# test_brd_gnd.net
KiCad netlist of a schematic drawn in EAGLE
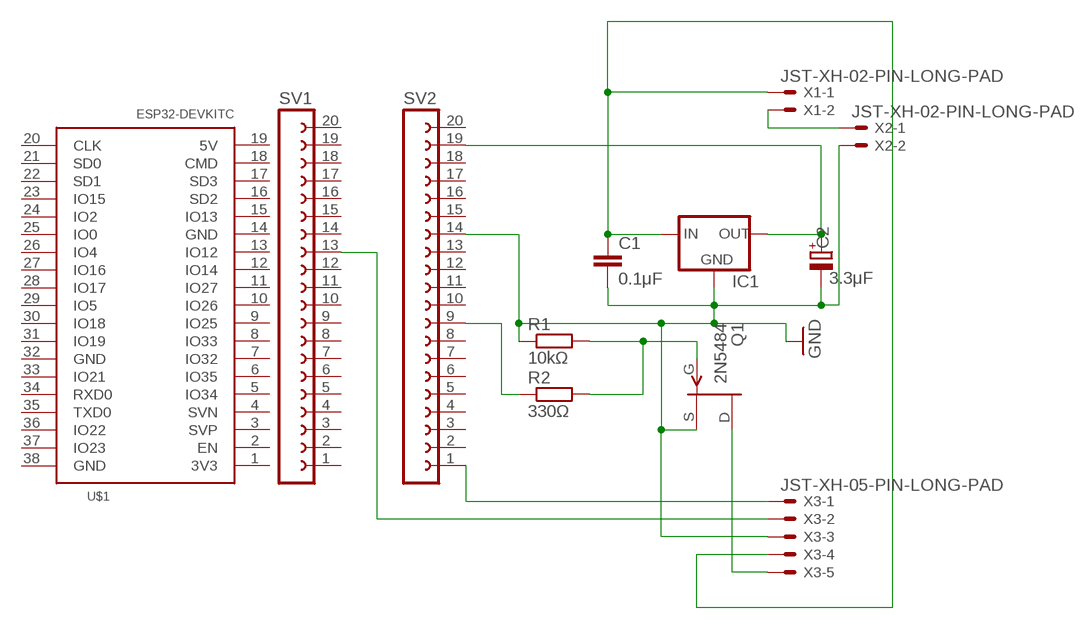
[diagram p0: schematic, sheet 1]

(export (version "E")
  (design (tool "Eeschema 10.0.6"))
  (components
    (comp (ref "C1")
      (value "0.1μF")
      (footprint "eagle-import:C025-040X050")
      (libsource (lib "eagle-import") (part "C-EU025-040X050"))
    )
    (comp (ref "C2")
      (value "3.3μF")
      (footprint "eagle-import:E2,5-5")
      (libsource (lib "eagle-import") (part "CPOL-EUE2.5-5"))
    )
    (comp (ref "IC1")
      (value "78XXS")
      (footprint "eagle-import:78XXS")
      (libsource (lib "eagle-import") (part "78XXS"))
    )
    (comp (ref "Q1")
      (value "2N5484")
      (footprint "eagle-import:TO92-")
      (libsource (lib "eagle-import") (part "?5482N4"))
    )
    (comp (ref "R1")
      (value "10kΩ")
      (footprint "eagle-import:0207_10")
      (libsource (lib "eagle-import") (part "R-EU_0207/10"))
    )
    (comp (ref "R2")
      (value "330Ω")
      (footprint "eagle-import:0207_10")
      (libsource (lib "eagle-import") (part "R-EU_0207/10"))
    )
    (comp (ref "SV1")
      (value "FE20-1")
      (footprint "eagle-import:FE20")
      (libsource (lib "eagle-import") (part "FE20-1"))
    )
    (comp (ref "SV2")
      (value "FE20-1")
      (footprint "eagle-import:FE20")
      (libsource (lib "eagle-import") (part "FE20-1"))
    )
    (comp (ref "U$1")
      (value "ESP32DEVKITC")
      (footprint "eagle-import:ESP32-DEVKITC")
      (libsource (lib "eagle-import") (part "ESP32DEVKITC"))
    )
    (comp (ref "X1")
      (value "JST-XH-02-PIN-LONG-PAD")
      (footprint "eagle-import:JST-XH-02-PACKAGE-LONG-PAD")
      (libsource (lib "eagle-import") (part "JST-XH-02-PIN-LONG-PAD"))
    )
    (comp (ref "X2")
      (value "JST-XH-02-PIN-LONG-PAD")
      (footprint "eagle-import:JST-XH-02-PACKAGE-LONG-PAD")
      (libsource (lib "eagle-import") (part "JST-XH-02-PIN-LONG-PAD"))
    )
    (comp (ref "X3")
      (value "JST-XH-05-PIN-LONG-PAD")
      (footprint "eagle-import:JST-XH-05-PACKAGE-LONG-PAD")
      (libsource (lib "eagle-import") (part "JST-XH-05-PIN-LONG-PAD"))
    )
  )
  (nets
    (net (code "1") (name "GND") (class "Default")
      (node (ref "C1") (pin "2") (pinfunction "2_2") (pintype "passive"))
      (node (ref "C2") (pin "-") (pinfunction "-_-") (pintype "passive"))
      (node (ref "IC1") (pin "GND") (pinfunction "GND_GND") (pintype "input"))
      (node (ref "Q1") (pin "2") (pinfunction "S_2") (pintype "passive"))
      (node (ref "R1") (pin "1") (pinfunction "1_1") (pintype "passive"))
      (node (ref "SV2") (pin "14") (pinfunction "14_14") (pintype "passive"))
      (node (ref "X2") (pin "2") (pinfunction "S_2") (pintype "passive"))
      (node (ref "X3") (pin "3") (pinfunction "S_3") (pintype "passive"))
    )
    (net (code "2") (name "Net-(C2-Pad+)") (class "Default")
      (node (ref "C2") (pin "+") (pinfunction "+_+") (pintype "passive"))
      (node (ref "IC1") (pin "OUT") (pinfunction "OUT_OUT") (pintype "passive"))
      (node (ref "SV2") (pin "19") (pinfunction "19_19") (pintype "passive"))
    )
    (net (code "3") (name "Net-(Q1-D)") (class "Default")
      (node (ref "Q1") (pin "3") (pinfunction "D_3") (pintype "passive"))
      (node (ref "X3") (pin "5") (pinfunction "S_5") (pintype "passive"))
    )
    (net (code "4") (name "Net-(Q1-G)") (class "Default")
      (node (ref "Q1") (pin "1") (pinfunction "G_1") (pintype "passive"))
      (node (ref "R1") (pin "2") (pinfunction "2_2") (pintype "passive"))
      (node (ref "R2") (pin "2") (pinfunction "2_2") (pintype "passive"))
    )
    (net (code "5") (name "Net-(R2-Pad1)") (class "Default")
      (node (ref "R2") (pin "1") (pinfunction "1_1") (pintype "passive"))
      (node (ref "SV2") (pin "9") (pinfunction "9_9") (pintype "passive"))
    )
    (net (code "6") (name "Net-(X1A-S)") (class "Default")
      (node (ref "C1") (pin "1") (pinfunction "1_1") (pintype "passive"))
      (node (ref "IC1") (pin "IN") (pinfunction "IN_IN") (pintype "input"))
      (node (ref "X1") (pin "1") (pinfunction "S_1") (pintype "passive"))
      (node (ref "X3") (pin "4") (pinfunction "S_4") (pintype "passive"))
    )
    (net (code "7") (name "Net-(X1B-S)") (class "Default")
      (node (ref "X1") (pin "2") (pinfunction "S_2") (pintype "passive"))
      (node (ref "X2") (pin "1") (pinfunction "S_1") (pintype "passive"))
    )
    (net (code "8") (name "Net-(X3A-S)") (class "Default")
      (node (ref "SV2") (pin "1") (pinfunction "1_1") (pintype "passive"))
      (node (ref "X3") (pin "1") (pinfunction "S_1") (pintype "passive"))
    )
    (net (code "9") (name "Net-(X3B-S)") (class "Default")
      (node (ref "SV1") (pin "13") (pinfunction "13_13") (pintype "passive"))
      (node (ref "X3") (pin "2") (pinfunction "S_2") (pintype "passive"))
    )
    (net (code "10") (name "unconnected-(SV1-Pad1)") (class "Default")
      (node (ref "SV1") (pin "1") (pinfunction "1_1") (pintype "passive"))
    )
    (net (code "11") (name "unconnected-(SV1-Pad2)") (class "Default")
      (node (ref "SV1") (pin "2") (pinfunction "2_2") (pintype "passive"))
    )
    (net (code "12") (name "unconnected-(SV1-Pad3)") (class "Default")
      (node (ref "SV1") (pin "3") (pinfunction "3_3") (pintype "passive"))
    )
    (net (code "13") (name "unconnected-(SV1-Pad4)") (class "Default")
      (node (ref "SV1") (pin "4") (pinfunction "4_4") (pintype "passive"))
    )
    (net (code "14") (name "unconnected-(SV1-Pad5)") (class "Default")
      (node (ref "SV1") (pin "5") (pinfunction "5_5") (pintype "passive"))
    )
    (net (code "15") (name "unconnected-(SV1-Pad6)") (class "Default")
      (node (ref "SV1") (pin "6") (pinfunction "6_6") (pintype "passive"))
    )
    (net (code "16") (name "unconnected-(SV1-Pad7)") (class "Default")
      (node (ref "SV1") (pin "7") (pinfunction "7_7") (pintype "passive"))
    )
    (net (code "17") (name "unconnected-(SV1-Pad8)") (class "Default")
      (node (ref "SV1") (pin "8") (pinfunction "8_8") (pintype "passive"))
    )
    (net (code "18") (name "unconnected-(SV1-Pad9)") (class "Default")
      (node (ref "SV1") (pin "9") (pinfunction "9_9") (pintype "passive"))
    )
    (net (code "19") (name "unconnected-(SV1-Pad10)") (class "Default")
      (node (ref "SV1") (pin "10") (pinfunction "10_10") (pintype "passive"))
    )
    (net (code "20") (name "unconnected-(SV1-Pad11)") (class "Default")
      (node (ref "SV1") (pin "11") (pinfunction "11_11") (pintype "passive"))
    )
    (net (code "21") (name "unconnected-(SV1-Pad12)") (class "Default")
      (node (ref "SV1") (pin "12") (pinfunction "12_12") (pintype "passive"))
    )
    (net (code "22") (name "unconnected-(SV1-Pad14)") (class "Default")
      (node (ref "SV1") (pin "14") (pinfunction "14_14") (pintype "passive"))
    )
    (net (code "23") (name "unconnected-(SV1-Pad15)") (class "Default")
      (node (ref "SV1") (pin "15") (pinfunction "15_15") (pintype "passive"))
    )
    (net (code "24") (name "unconnected-(SV1-Pad16)") (class "Default")
      (node (ref "SV1") (pin "16") (pinfunction "16_16") (pintype "passive"))
    )
    (net (code "25") (name "unconnected-(SV1-Pad17)") (class "Default")
      (node (ref "SV1") (pin "17") (pinfunction "17_17") (pintype "passive"))
    )
    (net (code "26") (name "unconnected-(SV1-Pad18)") (class "Default")
      (node (ref "SV1") (pin "18") (pinfunction "18_18") (pintype "passive"))
    )
    (net (code "27") (name "unconnected-(SV1-Pad19)") (class "Default")
      (node (ref "SV1") (pin "19") (pinfunction "19_19") (pintype "passive"))
    )
    (net (code "28") (name "unconnected-(SV1-Pad20)") (class "Default")
      (node (ref "SV1") (pin "20") (pinfunction "20_20") (pintype "passive"))
    )
    (net (code "29") (name "unconnected-(SV2-Pad2)") (class "Default")
      (node (ref "SV2") (pin "2") (pinfunction "2_2") (pintype "passive"))
    )
    (net (code "30") (name "unconnected-(SV2-Pad3)") (class "Default")
      (node (ref "SV2") (pin "3") (pinfunction "3_3") (pintype "passive"))
    )
    (net (code "31") (name "unconnected-(SV2-Pad4)") (class "Default")
      (node (ref "SV2") (pin "4") (pinfunction "4_4") (pintype "passive"))
    )
    (net (code "32") (name "unconnected-(SV2-Pad5)") (class "Default")
      (node (ref "SV2") (pin "5") (pinfunction "5_5") (pintype "passive"))
    )
    (net (code "33") (name "unconnected-(SV2-Pad6)") (class "Default")
      (node (ref "SV2") (pin "6") (pinfunction "6_6") (pintype "passive"))
    )
    (net (code "34") (name "unconnected-(SV2-Pad7)") (class "Default")
      (node (ref "SV2") (pin "7") (pinfunction "7_7") (pintype "passive"))
    )
    (net (code "35") (name "unconnected-(SV2-Pad8)") (class "Default")
      (node (ref "SV2") (pin "8") (pinfunction "8_8") (pintype "passive"))
    )
    (net (code "36") (name "unconnected-(SV2-Pad10)") (class "Default")
      (node (ref "SV2") (pin "10") (pinfunction "10_10") (pintype "passive"))
    )
    (net (code "37") (name "unconnected-(SV2-Pad11)") (class "Default")
      (node (ref "SV2") (pin "11") (pinfunction "11_11") (pintype "passive"))
    )
    (net (code "38") (name "unconnected-(SV2-Pad12)") (class "Default")
      (node (ref "SV2") (pin "12") (pinfunction "12_12") (pintype "passive"))
    )
    (net (code "39") (name "unconnected-(SV2-Pad13)") (class "Default")
      (node (ref "SV2") (pin "13") (pinfunction "13_13") (pintype "passive"))
    )
    (net (code "40") (name "unconnected-(SV2-Pad15)") (class "Default")
      (node (ref "SV2") (pin "15") (pinfunction "15_15") (pintype "passive"))
    )
    (net (code "41") (name "unconnected-(SV2-Pad16)") (class "Default")
      (node (ref "SV2") (pin "16") (pinfunction "16_16") (pintype "passive"))
    )
    (net (code "42") (name "unconnected-(SV2-Pad17)") (class "Default")
      (node (ref "SV2") (pin "17") (pinfunction "17_17") (pintype "passive"))
    )
    (net (code "43") (name "unconnected-(SV2-Pad18)") (class "Default")
      (node (ref "SV2") (pin "18") (pinfunction "18_18") (pintype "passive"))
    )
    (net (code "44") (name "unconnected-(SV2-Pad20)") (class "Default")
      (node (ref "SV2") (pin "20") (pinfunction "20_20") (pintype "passive"))
    )
    (net (code "45") (name "unconnected-(U$1-3V3-Pad1)") (class "Default")
      (node (ref "U$1") (pin "1") (pinfunction "3V3_1") (pintype "bidirectional"))
    )
    (net (code "46") (name "unconnected-(U$1-5V-Pad19)") (class "Default")
      (node (ref "U$1") (pin "19") (pinfunction "5V_19") (pintype "bidirectional"))
    )
    (net (code "47") (name "unconnected-(U$1-CLK-Pad20)") (class "Default")
      (node (ref "U$1") (pin "20") (pinfunction "CLK_20") (pintype "bidirectional"))
    )
    (net (code "48") (name "unconnected-(U$1-CMD-Pad18)") (class "Default")
      (node (ref "U$1") (pin "18") (pinfunction "CMD_18") (pintype "bidirectional"))
    )
    (net (code "49") (name "unconnected-(U$1-EN-Pad2)") (class "Default")
      (node (ref "U$1") (pin "2") (pinfunction "EN_2") (pintype "bidirectional"))
    )
    (net (code "50") (name "unconnected-(U$1-GND-Pad14)") (class "Default")
      (node (ref "U$1") (pin "14") (pinfunction "GND_14") (pintype "bidirectional"))
    )
    (net (code "51") (name "unconnected-(U$1-GND-Pad32)") (class "Default")
      (node (ref "U$1") (pin "32") (pinfunction "GND_32") (pintype "bidirectional"))
    )
    (net (code "52") (name "unconnected-(U$1-GND-Pad38)") (class "Default")
      (node (ref "U$1") (pin "38") (pinfunction "GND_38") (pintype "bidirectional"))
    )
    (net (code "53") (name "unconnected-(U$1-IO0-Pad25)") (class "Default")
      (node (ref "U$1") (pin "25") (pinfunction "IO0_25") (pintype "bidirectional"))
    )
    (net (code "54") (name "unconnected-(U$1-IO2-Pad24)") (class "Default")
      (node (ref "U$1") (pin "24") (pinfunction "IO2_24") (pintype "bidirectional"))
    )
    (net (code "55") (name "unconnected-(U$1-IO4-Pad26)") (class "Default")
      (node (ref "U$1") (pin "26") (pinfunction "IO4_26") (pintype "bidirectional"))
    )
    (net (code "56") (name "unconnected-(U$1-IO5-Pad29)") (class "Default")
      (node (ref "U$1") (pin "29") (pinfunction "IO5_29") (pintype "bidirectional"))
    )
    (net (code "57") (name "unconnected-(U$1-IO12-Pad13)") (class "Default")
      (node (ref "U$1") (pin "13") (pinfunction "IO12_13") (pintype "bidirectional"))
    )
    (net (code "58") (name "unconnected-(U$1-IO13-Pad15)") (class "Default")
      (node (ref "U$1") (pin "15") (pinfunction "IO13_15") (pintype "bidirectional"))
    )
    (net (code "59") (name "unconnected-(U$1-IO14-Pad12)") (class "Default")
      (node (ref "U$1") (pin "12") (pinfunction "IO14_12") (pintype "bidirectional"))
    )
    (net (code "60") (name "unconnected-(U$1-IO15-Pad23)") (class "Default")
      (node (ref "U$1") (pin "23") (pinfunction "IO15_23") (pintype "bidirectional"))
    )
    (net (code "61") (name "unconnected-(U$1-IO16-Pad27)") (class "Default")
      (node (ref "U$1") (pin "27") (pinfunction "IO16_27") (pintype "bidirectional"))
    )
    (net (code "62") (name "unconnected-(U$1-IO17-Pad28)") (class "Default")
      (node (ref "U$1") (pin "28") (pinfunction "IO17_28") (pintype "bidirectional"))
    )
    (net (code "63") (name "unconnected-(U$1-IO18-Pad30)") (class "Default")
      (node (ref "U$1") (pin "30") (pinfunction "IO18_30") (pintype "bidirectional"))
    )
    (net (code "64") (name "unconnected-(U$1-IO19-Pad31)") (class "Default")
      (node (ref "U$1") (pin "31") (pinfunction "IO19_31") (pintype "bidirectional"))
    )
    (net (code "65") (name "unconnected-(U$1-IO21-Pad33)") (class "Default")
      (node (ref "U$1") (pin "33") (pinfunction "IO21_33") (pintype "bidirectional"))
    )
    (net (code "66") (name "unconnected-(U$1-IO22-Pad36)") (class "Default")
      (node (ref "U$1") (pin "36") (pinfunction "IO22_36") (pintype "bidirectional"))
    )
    (net (code "67") (name "unconnected-(U$1-IO23-Pad37)") (class "Default")
      (node (ref "U$1") (pin "37") (pinfunction "IO23_37") (pintype "bidirectional"))
    )
    (net (code "68") (name "unconnected-(U$1-IO25-Pad9)") (class "Default")
      (node (ref "U$1") (pin "9") (pinfunction "IO25_9") (pintype "bidirectional"))
    )
    (net (code "69") (name "unconnected-(U$1-IO26-Pad10)") (class "Default")
      (node (ref "U$1") (pin "10") (pinfunction "IO26_10") (pintype "bidirectional"))
    )
    (net (code "70") (name "unconnected-(U$1-IO27-Pad11)") (class "Default")
      (node (ref "U$1") (pin "11") (pinfunction "IO27_11") (pintype "bidirectional"))
    )
    (net (code "71") (name "unconnected-(U$1-IO32-Pad7)") (class "Default")
      (node (ref "U$1") (pin "7") (pinfunction "IO32_7") (pintype "bidirectional"))
    )
    (net (code "72") (name "unconnected-(U$1-IO33-Pad8)") (class "Default")
      (node (ref "U$1") (pin "8") (pinfunction "IO33_8") (pintype "bidirectional"))
    )
    (net (code "73") (name "unconnected-(U$1-IO34-Pad5)") (class "Default")
      (node (ref "U$1") (pin "5") (pinfunction "IO34_5") (pintype "bidirectional"))
    )
    (net (code "74") (name "unconnected-(U$1-IO35-Pad6)") (class "Default")
      (node (ref "U$1") (pin "6") (pinfunction "IO35_6") (pintype "bidirectional"))
    )
    (net (code "75") (name "unconnected-(U$1-RXD0-Pad34)") (class "Default")
      (node (ref "U$1") (pin "34") (pinfunction "RXD0_34") (pintype "bidirectional"))
    )
    (net (code "76") (name "unconnected-(U$1-SD0-Pad21)") (class "Default")
      (node (ref "U$1") (pin "21") (pinfunction "SD0_21") (pintype "bidirectional"))
    )
    (net (code "77") (name "unconnected-(U$1-SD1-Pad22)") (class "Default")
      (node (ref "U$1") (pin "22") (pinfunction "SD1_22") (pintype "bidirectional"))
    )
    (net (code "78") (name "unconnected-(U$1-SD2-Pad16)") (class "Default")
      (node (ref "U$1") (pin "16") (pinfunction "SD2_16") (pintype "bidirectional"))
    )
    (net (code "79") (name "unconnected-(U$1-SD3-Pad17)") (class "Default")
      (node (ref "U$1") (pin "17") (pinfunction "SD3_17") (pintype "bidirectional"))
    )
    (net (code "80") (name "unconnected-(U$1-SVN-Pad4)") (class "Default")
      (node (ref "U$1") (pin "4") (pinfunction "SVN_4") (pintype "bidirectional"))
    )
    (net (code "81") (name "unconnected-(U$1-SVP-Pad3)") (class "Default")
      (node (ref "U$1") (pin "3") (pinfunction "SVP_3") (pintype "bidirectional"))
    )
    (net (code "82") (name "unconnected-(U$1-TXD0-Pad35)") (class "Default")
      (node (ref "U$1") (pin "35") (pinfunction "TXD0_35") (pintype "bidirectional"))
    )
  )
)
